# LED.net
KiCad netlist of a schematic drawn in Altium Designer
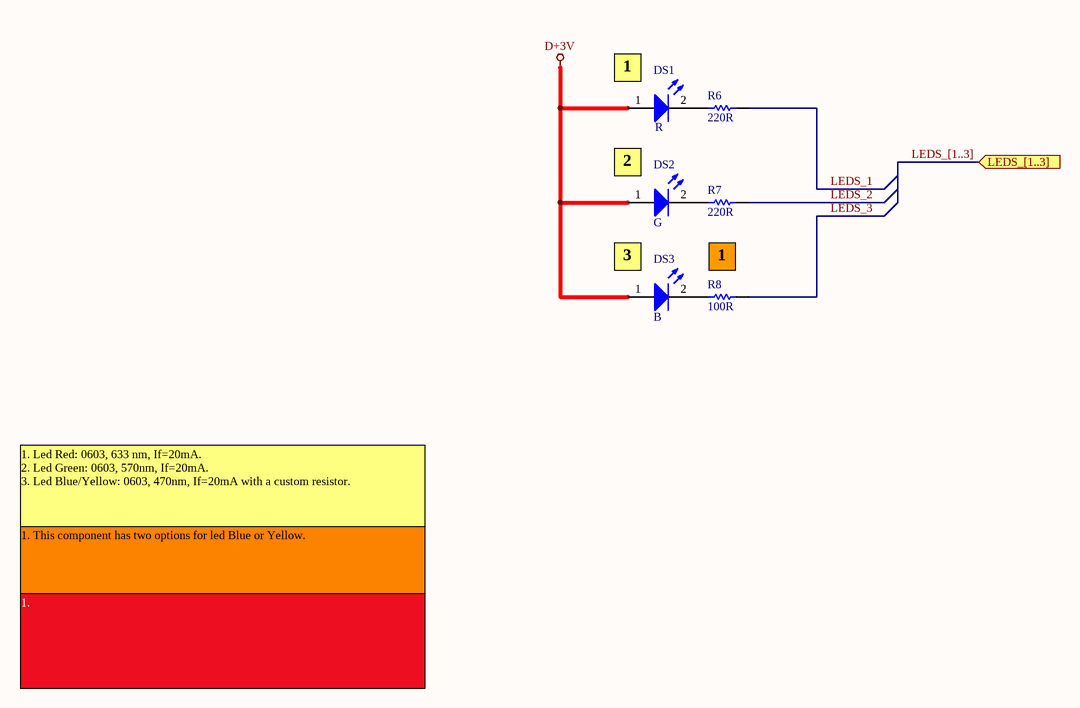
[diagram p0: LED.SchDoc]

(export (version "E")
  (design (tool "Eeschema 10.0.6"))
  (components
    (comp (ref "DS1")
      (value "R")
      (footprint "LED0603")
      (description "LED 1.6X0.8MM 631NM RED CLR SMD")
      (libsource (lib "Z1_Project") (part "LED2"))
    )
    (comp (ref "DS2")
      (value "G")
      (footprint "LED0603")
      (description "LED CHIPLED 570NM GREEN 0603 SMD")
      (libsource (lib "Z1_Project") (part "LED2"))
    )
    (comp (ref "DS3")
      (value "B")
      (footprint "LED0603")
      (description "LED 1.6X0.8MM 470NM BLUE CLR SMD")
      (libsource (lib "Z1_Project") (part "LED2"))
    )
    (comp (ref "R6")
      (value "220R")
      (footprint "CR-0402-AL")
      (description "Semiconductor Resistor")
      (fields (field (name "MANUFACTURER") "Generic Components") (field (name "Comment") "Res Semi"))
      (libsource (lib "Z1_Project") (part "Res Semi"))
    )
    (comp (ref "R7")
      (value "220R")
      (footprint "CR-0402-AL")
      (description "Semiconductor Resistor")
      (fields (field (name "MANUFACTURER") "Generic Components") (field (name "Comment") "Res Semi"))
      (libsource (lib "Z1_Project") (part "Res Semi"))
    )
    (comp (ref "R8")
      (value "100R")
      (footprint "CR-0402-AL")
      (description "Semiconductor Resistor")
      (fields (field (name "MANUFACTURER") "Generic Components") (field (name "Comment") "Res Semi"))
      (libsource (lib "Z1_Project") (part "Res Semi"))
    )
  )
  (nets
    (net (code "1") (name "/LEDS_1") (class "Default")
      (node (ref "R6") (pin "1") (pinfunction "1_1") (pintype "passive"))
    )
    (net (code "2") (name "/LEDS_2") (class "Default")
      (node (ref "R7") (pin "2") (pinfunction "2_2") (pintype "passive"))
    )
    (net (code "3") (name "/LEDS_3") (class "Default")
      (node (ref "R8") (pin "2") (pinfunction "2_2") (pintype "passive"))
    )
    (net (code "5") (name "D+3V") (class "Default")
      (node (ref "DS1") (pin "1") (pinfunction "A_1") (pintype "passive"))
      (node (ref "DS2") (pin "1") (pinfunction "A_1") (pintype "passive"))
      (node (ref "DS3") (pin "1") (pinfunction "A_1") (pintype "passive"))
    )
    (net (code "6") (name "Net-(DS1-K)") (class "Default")
      (node (ref "DS1") (pin "2") (pinfunction "K_2") (pintype "passive"))
      (node (ref "R6") (pin "2") (pinfunction "2_2") (pintype "passive"))
    )
    (net (code "7") (name "Net-(DS2-K)") (class "Default")
      (node (ref "DS2") (pin "2") (pinfunction "K_2") (pintype "passive"))
      (node (ref "R7") (pin "1") (pinfunction "1_1") (pintype "passive"))
    )
    (net (code "8") (name "Net-(DS3-K)") (class "Default")
      (node (ref "DS3") (pin "2") (pinfunction "K_2") (pintype "passive"))
      (node (ref "R8") (pin "1") (pinfunction "1_1") (pintype "passive"))
    )
  )
)
